# FAN-plus30-SHIM.net
KiCad netlist of a schematic drawn in EAGLE
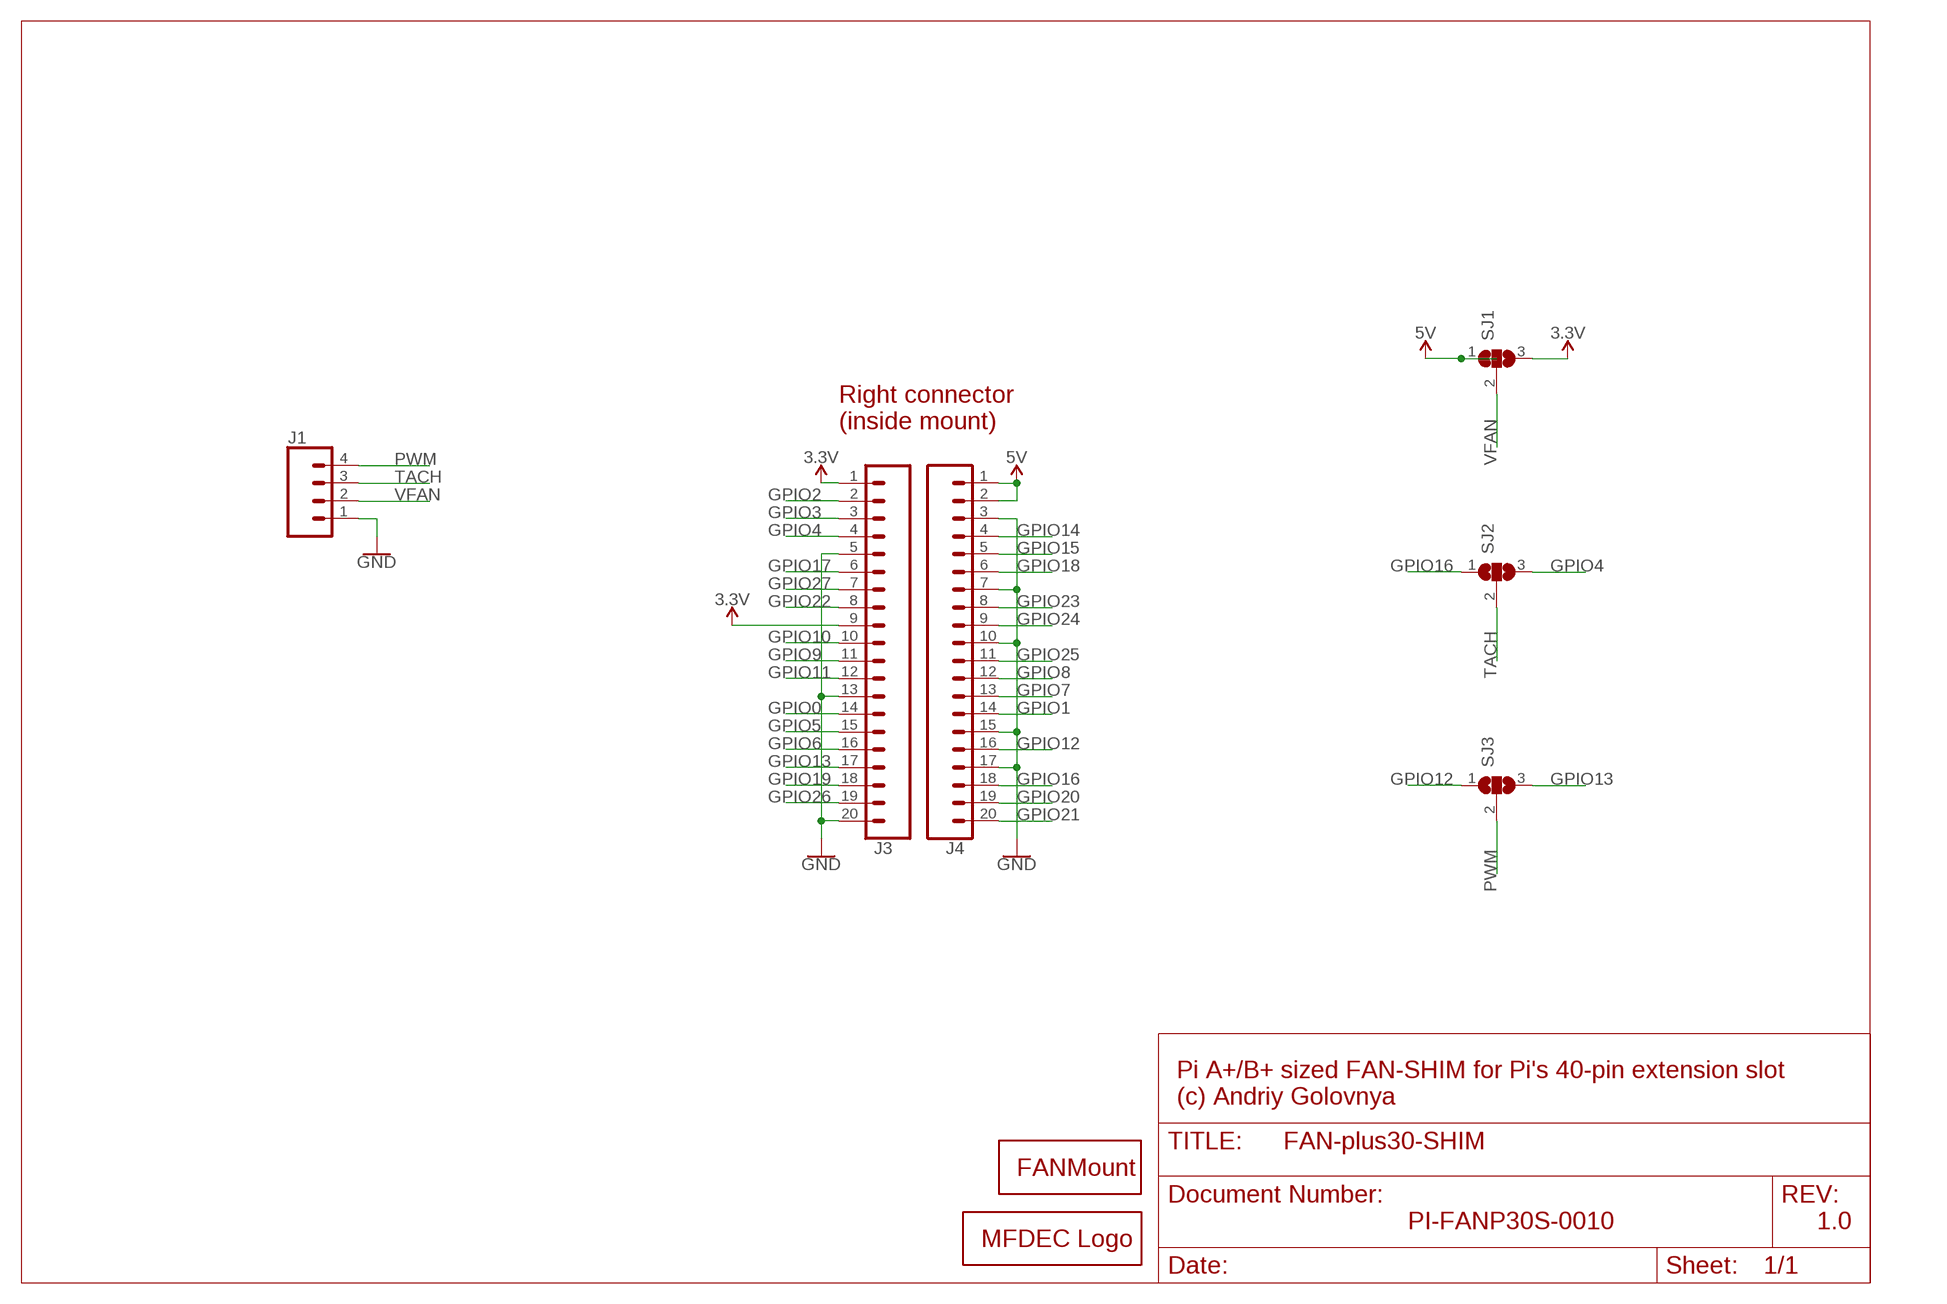
[diagram p0: schematic, sheet 1]

(export (version "E")
  (design (tool "Eeschema 10.0.6"))
  (components
    (comp (ref "FAN1")
      (value "FAN30HO")
      (footprint "eagle-import:FAN30HO")
      (libsource (lib "eagle-import") (part "FAN30HO"))
    )
    (comp (ref "J1")
      (value "CONN_04")
      (footprint "eagle-import:1X04")
      (libsource (lib "eagle-import") (part "CONN_04"))
    )
    (comp (ref "J3")
      (value "CONN_20LOCK")
      (footprint "eagle-import:1X20_LOCK")
      (libsource (lib "eagle-import") (part "CONN_20LOCK"))
    )
    (comp (ref "J4")
      (value "CONN_20LOCK")
      (footprint "eagle-import:1X20_LOCK")
      (libsource (lib "eagle-import") (part "CONN_20LOCK"))
    )
    (comp (ref "LOGO1")
      (value "MFDECLOGO_L_40MM")
      (footprint "eagle-import:MFDEC_L_40MM")
      (libsource (lib "eagle-import") (part "MFDECLOGO_L_40MM"))
    )
    (comp (ref "SJ1")
      (value "SJ2")
      (footprint "eagle-import:SJ_2")
      (libsource (lib "eagle-import") (part "SJ2"))
    )
    (comp (ref "SJ2")
      (value "SJ2")
      (footprint "eagle-import:SJ_2")
      (libsource (lib "eagle-import") (part "SJ2"))
    )
    (comp (ref "SJ3")
      (value "SJ2")
      (footprint "eagle-import:SJ_2")
      (libsource (lib "eagle-import") (part "SJ2"))
    )
  )
  (nets
    (net (code "1") (name "/GPIO0") (class "Default")
      (node (ref "J3") (pin "14") (pinfunction "14_14") (pintype "passive"))
    )
    (net (code "2") (name "/GPIO1") (class "Default")
      (node (ref "J4") (pin "14") (pinfunction "14_14") (pintype "passive"))
    )
    (net (code "3") (name "/GPIO2") (class "Default")
      (node (ref "J3") (pin "2") (pinfunction "2_2") (pintype "passive"))
    )
    (net (code "4") (name "/GPIO3") (class "Default")
      (node (ref "J3") (pin "3") (pinfunction "3_3") (pintype "passive"))
    )
    (net (code "5") (name "/GPIO4") (class "Default")
      (node (ref "J3") (pin "4") (pinfunction "4_4") (pintype "passive"))
      (node (ref "SJ2") (pin "3") (pinfunction "3_3") (pintype "passive"))
    )
    (net (code "6") (name "/GPIO5") (class "Default")
      (node (ref "J3") (pin "15") (pinfunction "15_15") (pintype "passive"))
    )
    (net (code "7") (name "/GPIO6") (class "Default")
      (node (ref "J3") (pin "16") (pinfunction "16_16") (pintype "passive"))
    )
    (net (code "8") (name "/GPIO7") (class "Default")
      (node (ref "J4") (pin "13") (pinfunction "13_13") (pintype "passive"))
    )
    (net (code "9") (name "/GPIO8") (class "Default")
      (node (ref "J4") (pin "12") (pinfunction "12_12") (pintype "passive"))
    )
    (net (code "10") (name "/GPIO9") (class "Default")
      (node (ref "J3") (pin "11") (pinfunction "11_11") (pintype "passive"))
    )
    (net (code "11") (name "/GPIO10") (class "Default")
      (node (ref "J3") (pin "10") (pinfunction "10_10") (pintype "passive"))
    )
    (net (code "12") (name "/GPIO11") (class "Default")
      (node (ref "J3") (pin "12") (pinfunction "12_12") (pintype "passive"))
    )
    (net (code "13") (name "/GPIO12") (class "Default")
      (node (ref "J4") (pin "16") (pinfunction "16_16") (pintype "passive"))
      (node (ref "SJ3") (pin "1") (pinfunction "1_1") (pintype "passive"))
    )
    (net (code "14") (name "/GPIO13") (class "Default")
      (node (ref "J3") (pin "17") (pinfunction "17_17") (pintype "passive"))
      (node (ref "SJ3") (pin "3") (pinfunction "3_3") (pintype "passive"))
    )
    (net (code "15") (name "/GPIO14") (class "Default")
      (node (ref "J4") (pin "4") (pinfunction "4_4") (pintype "passive"))
    )
    (net (code "16") (name "/GPIO15") (class "Default")
      (node (ref "J4") (pin "5") (pinfunction "5_5") (pintype "passive"))
    )
    (net (code "17") (name "/GPIO16") (class "Default")
      (node (ref "J4") (pin "18") (pinfunction "18_18") (pintype "passive"))
      (node (ref "SJ2") (pin "1") (pinfunction "1_1") (pintype "passive"))
    )
    (net (code "18") (name "/GPIO17") (class "Default")
      (node (ref "J3") (pin "6") (pinfunction "6_6") (pintype "passive"))
    )
    (net (code "19") (name "/GPIO18") (class "Default")
      (node (ref "J4") (pin "6") (pinfunction "6_6") (pintype "passive"))
    )
    (net (code "20") (name "/GPIO19") (class "Default")
      (node (ref "J3") (pin "18") (pinfunction "18_18") (pintype "passive"))
    )
    (net (code "21") (name "/GPIO20") (class "Default")
      (node (ref "J4") (pin "19") (pinfunction "19_19") (pintype "passive"))
    )
    (net (code "22") (name "/GPIO21") (class "Default")
      (node (ref "J4") (pin "20") (pinfunction "20_20") (pintype "passive"))
    )
    (net (code "23") (name "/GPIO22") (class "Default")
      (node (ref "J3") (pin "8") (pinfunction "8_8") (pintype "passive"))
    )
    (net (code "24") (name "/GPIO23") (class "Default")
      (node (ref "J4") (pin "8") (pinfunction "8_8") (pintype "passive"))
    )
    (net (code "25") (name "/GPIO24") (class "Default")
      (node (ref "J4") (pin "9") (pinfunction "9_9") (pintype "passive"))
    )
    (net (code "26") (name "/GPIO25") (class "Default")
      (node (ref "J4") (pin "11") (pinfunction "11_11") (pintype "passive"))
    )
    (net (code "27") (name "/GPIO26") (class "Default")
      (node (ref "J3") (pin "19") (pinfunction "19_19") (pintype "passive"))
    )
    (net (code "28") (name "/GPIO27") (class "Default")
      (node (ref "J3") (pin "7") (pinfunction "7_7") (pintype "passive"))
    )
    (net (code "29") (name "/PWM") (class "Default")
      (node (ref "J1") (pin "4") (pinfunction "4_4") (pintype "passive"))
      (node (ref "SJ3") (pin "2") (pinfunction "2_2") (pintype "passive"))
    )
    (net (code "30") (name "/TACH") (class "Default")
      (node (ref "J1") (pin "3") (pinfunction "3_3") (pintype "passive"))
      (node (ref "SJ2") (pin "2") (pinfunction "2_2") (pintype "passive"))
    )
    (net (code "31") (name "/VFAN") (class "Default")
      (node (ref "J1") (pin "2") (pinfunction "2_2") (pintype "passive"))
      (node (ref "SJ1") (pin "2") (pinfunction "2_2") (pintype "passive"))
    )
    (net (code "32") (name "3.3V") (class "Default")
      (node (ref "J3") (pin "1") (pinfunction "1_1") (pintype "passive"))
      (node (ref "J3") (pin "9") (pinfunction "9_9") (pintype "passive"))
      (node (ref "SJ1") (pin "3") (pinfunction "3_3") (pintype "passive"))
    )
    (net (code "33") (name "5V") (class "Default")
      (node (ref "J4") (pin "1") (pinfunction "1_1") (pintype "passive"))
      (node (ref "J4") (pin "2") (pinfunction "2_2") (pintype "passive"))
      (node (ref "SJ1") (pin "1") (pinfunction "1_1") (pintype "passive"))
    )
    (net (code "34") (name "GND") (class "Default")
      (node (ref "J1") (pin "1") (pinfunction "1_1") (pintype "passive"))
      (node (ref "J3") (pin "13") (pinfunction "13_13") (pintype "passive"))
      (node (ref "J3") (pin "20") (pinfunction "20_20") (pintype "passive"))
      (node (ref "J3") (pin "5") (pinfunction "5_5") (pintype "passive"))
      (node (ref "J4") (pin "10") (pinfunction "10_10") (pintype "passive"))
      (node (ref "J4") (pin "15") (pinfunction "15_15") (pintype "passive"))
      (node (ref "J4") (pin "17") (pinfunction "17_17") (pintype "passive"))
      (node (ref "J4") (pin "3") (pinfunction "3_3") (pintype "passive"))
      (node (ref "J4") (pin "7") (pinfunction "7_7") (pintype "passive"))
    )
  )
)
